# ARM_Arduino_Mega_Board_v2.net
KiCad netlist of a schematic drawn in EAGLE
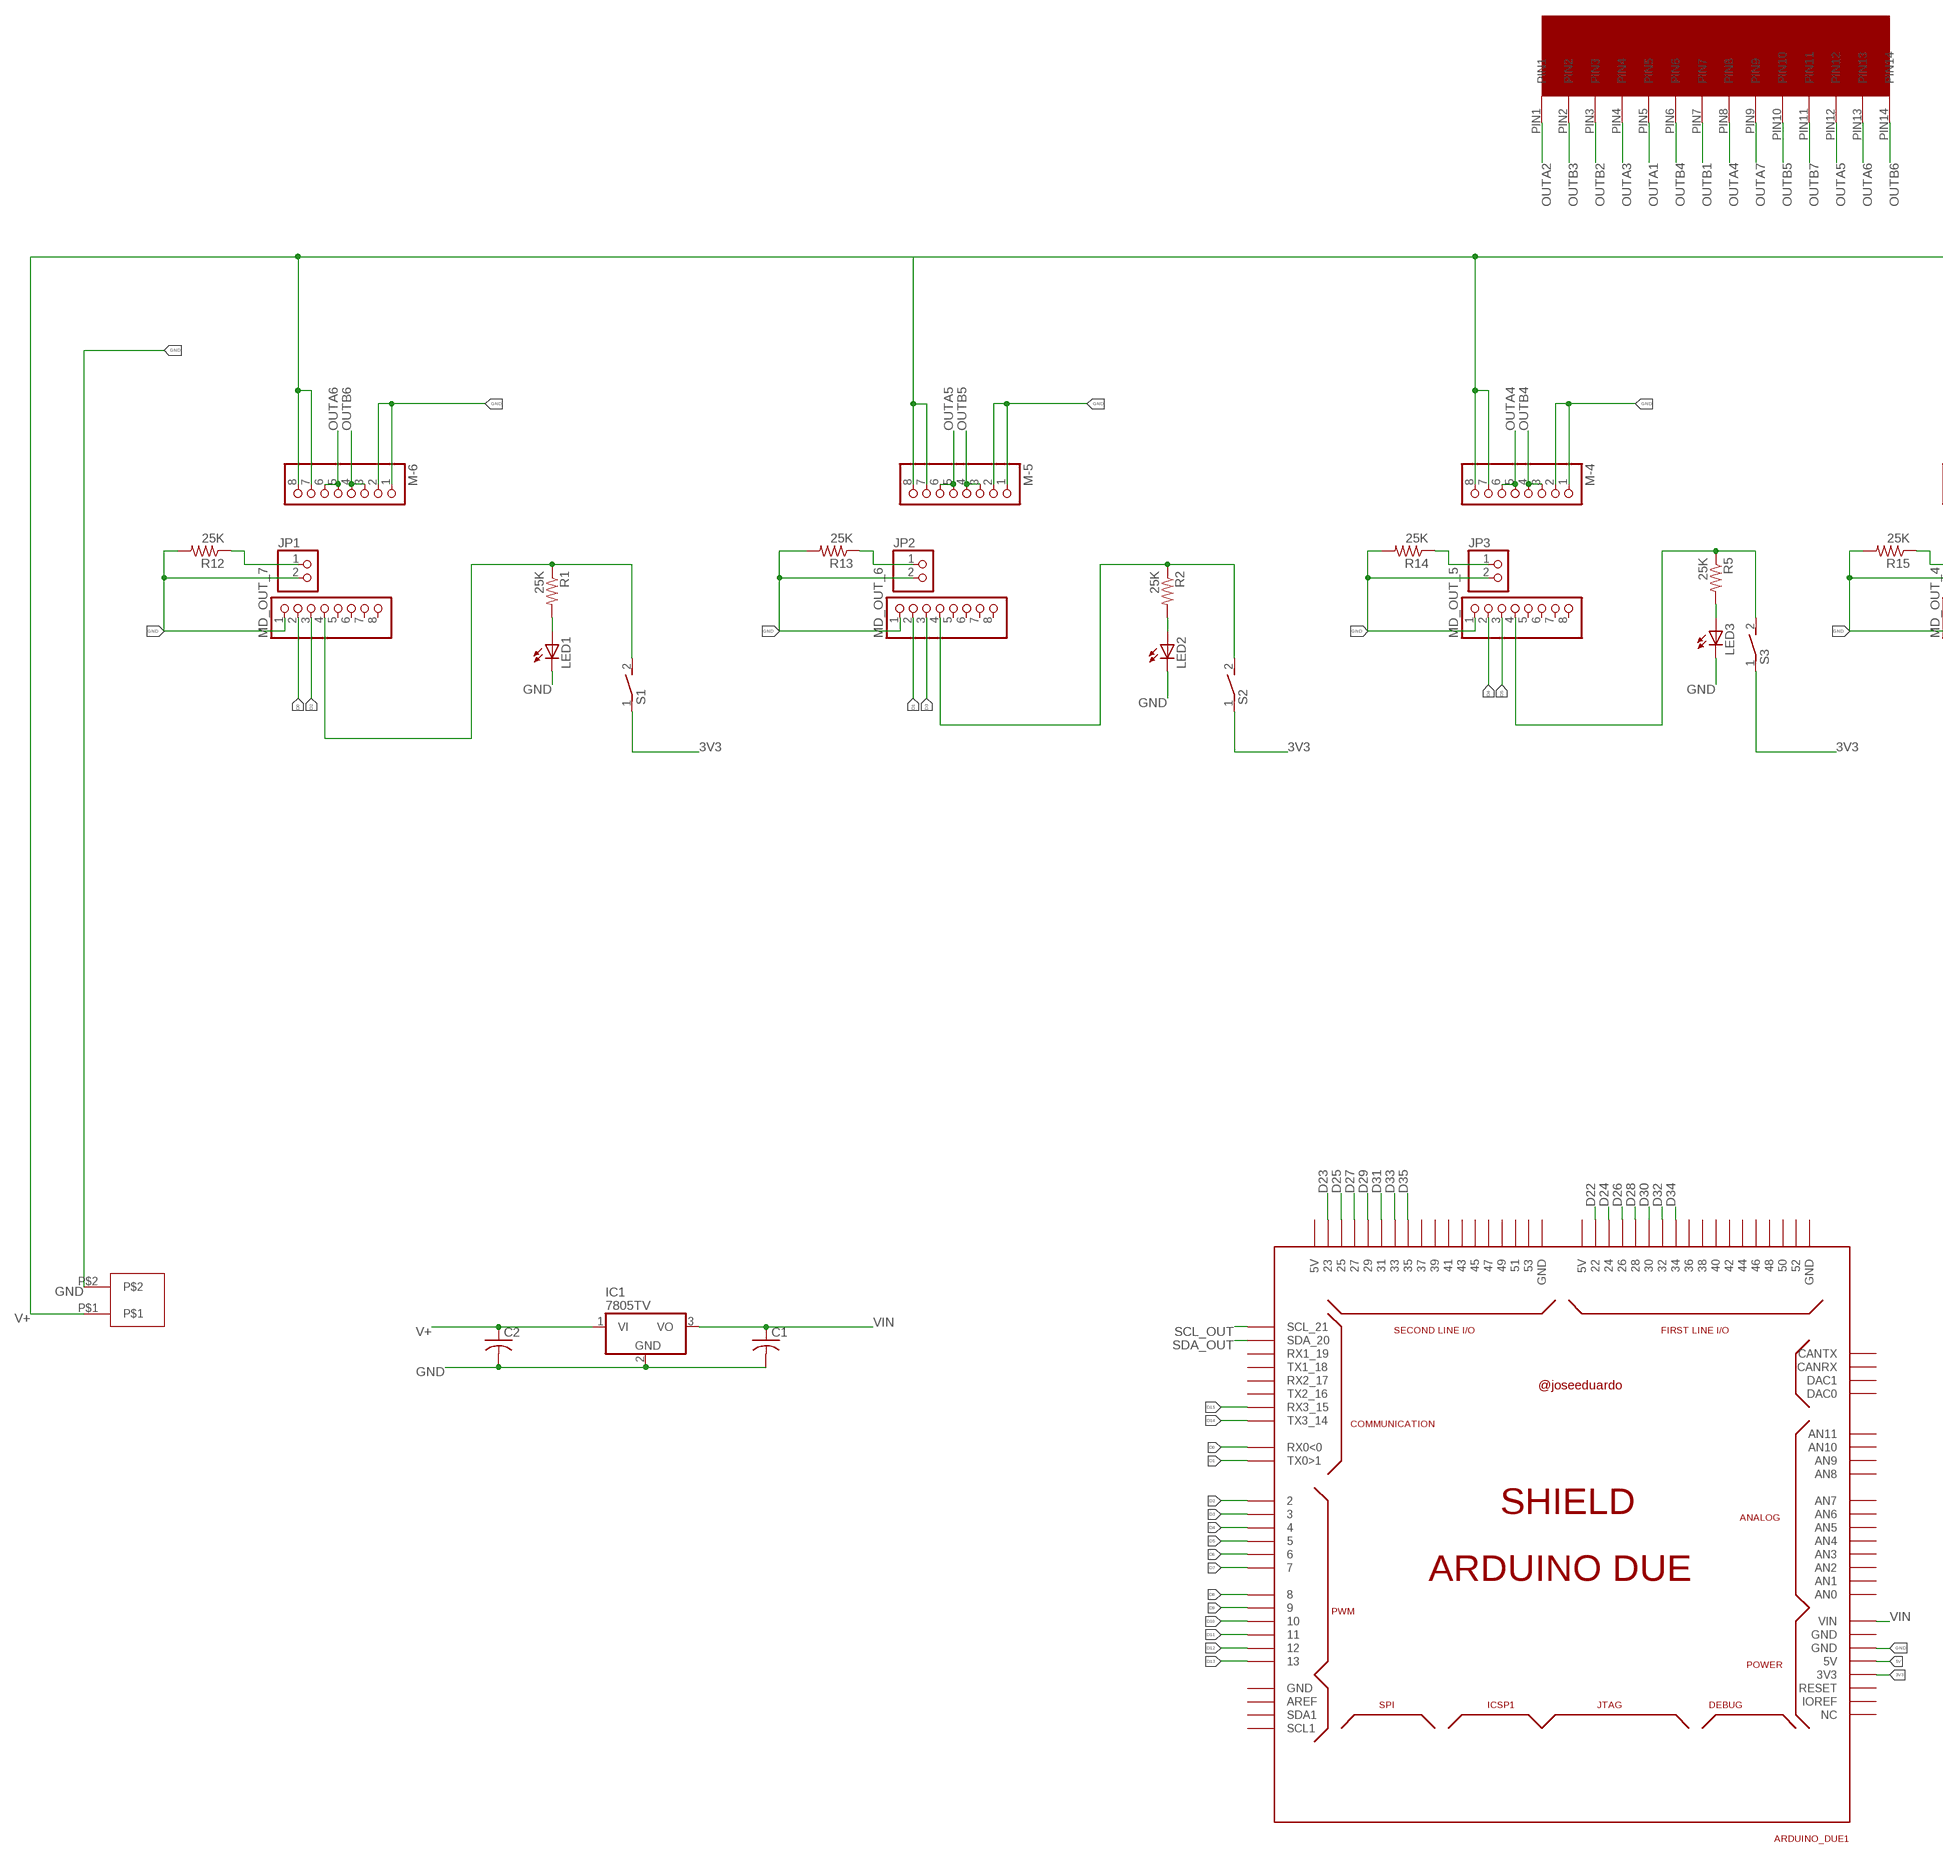
[diagram p0: schematic, sheet 1, part 1 of 2]
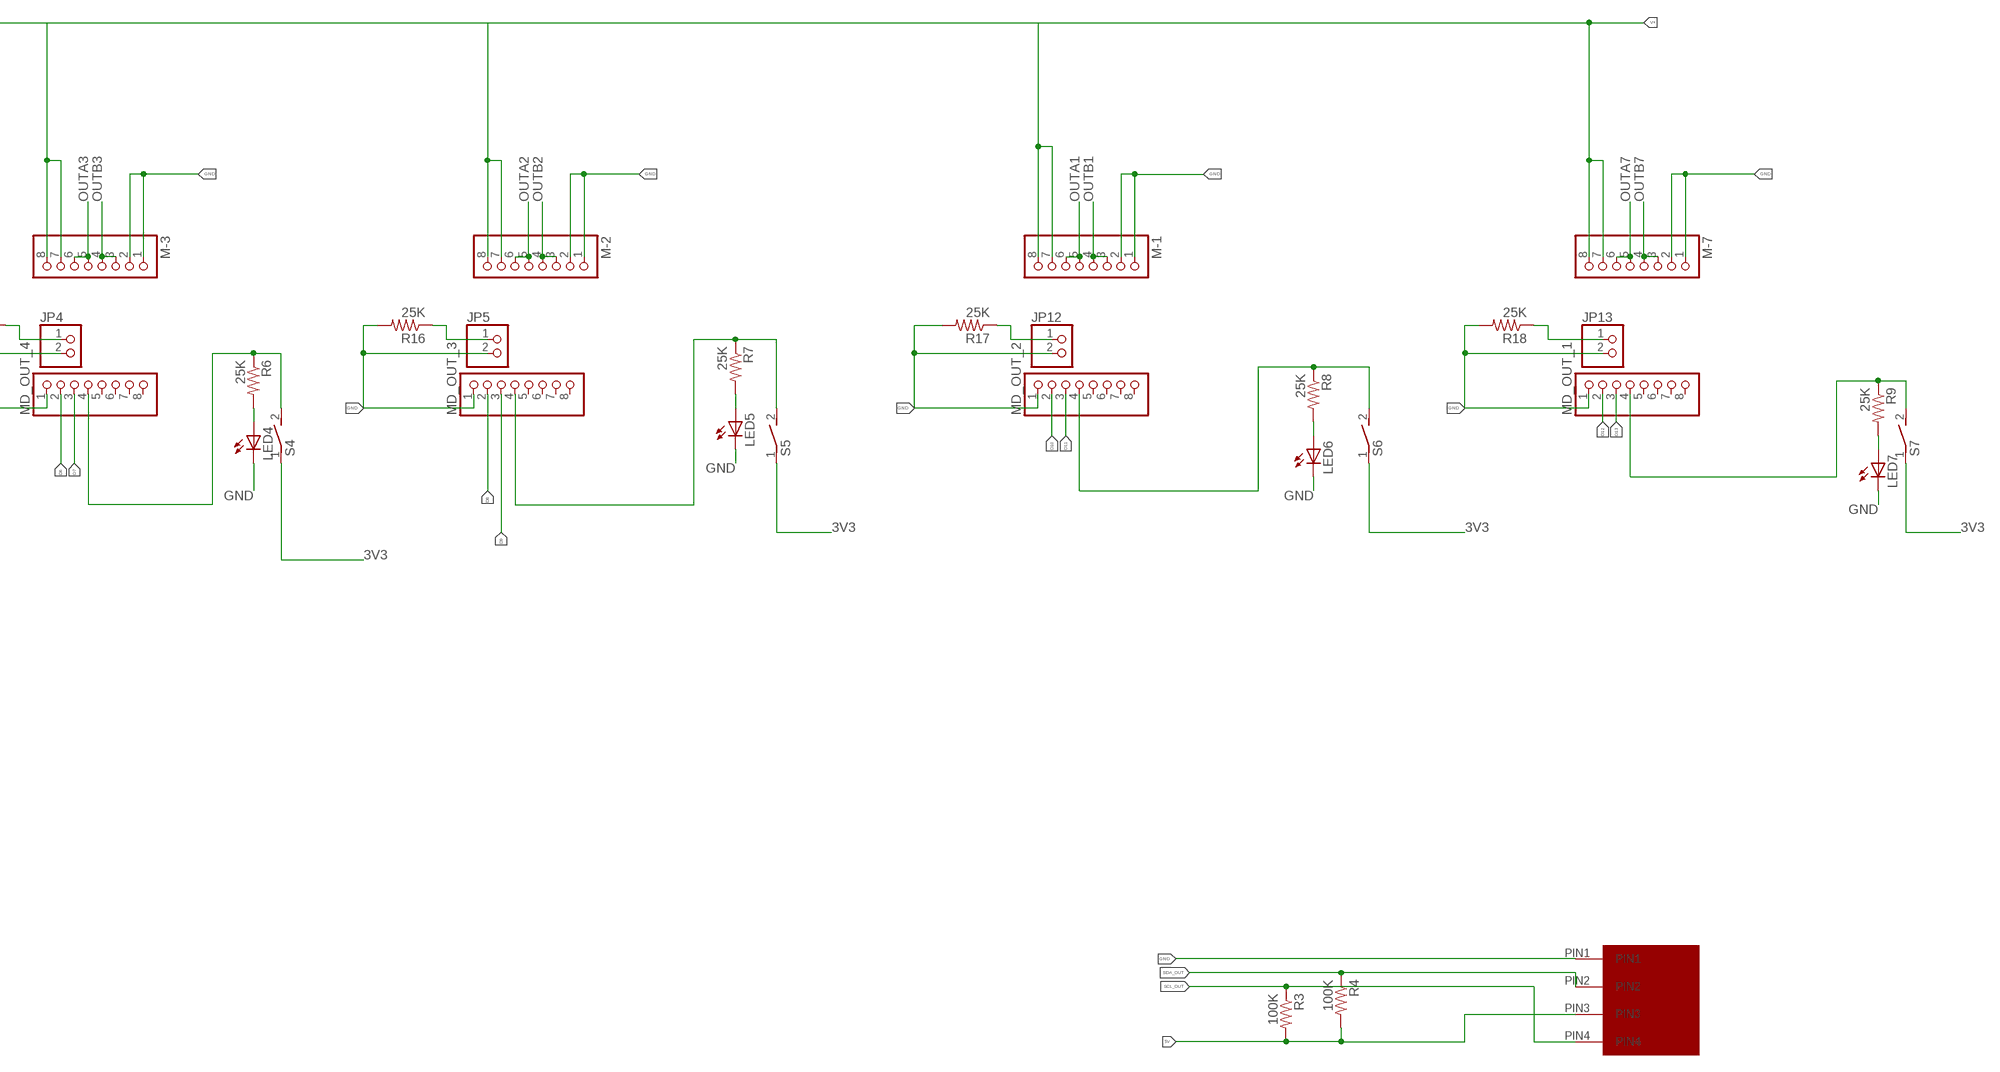
[diagram p1: schematic, sheet 1, part 2 of 2]

(export (version "E")
  (design (tool "Eeschema 10.0.6"))
  (components
    (comp (ref "ARDUINO_DUE1")
      (value "ARDUINO_DUE_SHIELD")
      (footprint "eagle-import:ARDUINO_DUE_SHIELD")
      (libsource (lib "eagle-import") (part "ARDUINO_DUE_SHIELD"))
    )
    (comp (ref "C1")
      (value "C-US050-045X075")
      (footprint "eagle-import:C050-045X075")
      (libsource (lib "eagle-import") (part "C-US050-045X075"))
    )
    (comp (ref "C2")
      (value "C-US050-045X075")
      (footprint "eagle-import:C050-045X075")
      (libsource (lib "eagle-import") (part "C-US050-045X075"))
    )
    (comp (ref "IC1")
      (value "7805TV")
      (footprint "eagle-import:TO220V")
      (libsource (lib "eagle-import") (part "78TV05"))
    )
    (comp (ref "JP1")
      (value "PINHD-1X2")
      (footprint "eagle-import:1X02")
      (libsource (lib "eagle-import") (part "PINHD-1X2"))
    )
    (comp (ref "JP2")
      (value "PINHD-1X2")
      (footprint "eagle-import:1X02")
      (libsource (lib "eagle-import") (part "PINHD-1X2"))
    )
    (comp (ref "JP3")
      (value "PINHD-1X2")
      (footprint "eagle-import:1X02")
      (libsource (lib "eagle-import") (part "PINHD-1X2"))
    )
    (comp (ref "JP4")
      (value "PINHD-1X2")
      (footprint "eagle-import:1X02")
      (libsource (lib "eagle-import") (part "PINHD-1X2"))
    )
    (comp (ref "JP5")
      (value "PINHD-1X2")
      (footprint "eagle-import:1X02")
      (libsource (lib "eagle-import") (part "PINHD-1X2"))
    )
    (comp (ref "JP12")
      (value "PINHD-1X2")
      (footprint "eagle-import:1X02")
      (libsource (lib "eagle-import") (part "PINHD-1X2"))
    )
    (comp (ref "JP13")
      (value "PINHD-1X2")
      (footprint "eagle-import:1X02")
      (libsource (lib "eagle-import") (part "PINHD-1X2"))
    )
    (comp (ref "LED1")
      (value "LEDCHIP-LED0603")
      (footprint "eagle-import:CHIP-LED0603")
      (libsource (lib "eagle-import") (part "LEDCHIP-LED0603"))
    )
    (comp (ref "LED2")
      (value "LEDCHIP-LED0603")
      (footprint "eagle-import:CHIP-LED0603")
      (libsource (lib "eagle-import") (part "LEDCHIP-LED0603"))
    )
    (comp (ref "LED3")
      (value "LEDCHIP-LED0603")
      (footprint "eagle-import:CHIP-LED0603")
      (libsource (lib "eagle-import") (part "LEDCHIP-LED0603"))
    )
    (comp (ref "LED4")
      (value "LEDCHIP-LED0603")
      (footprint "eagle-import:CHIP-LED0603")
      (libsource (lib "eagle-import") (part "LEDCHIP-LED0603"))
    )
    (comp (ref "LED5")
      (value "LEDCHIP-LED0603")
      (footprint "eagle-import:CHIP-LED0603")
      (libsource (lib "eagle-import") (part "LEDCHIP-LED0603"))
    )
    (comp (ref "LED6")
      (value "LEDCHIP-LED0603")
      (footprint "eagle-import:CHIP-LED0603")
      (libsource (lib "eagle-import") (part "LEDCHIP-LED0603"))
    )
    (comp (ref "LED7")
      (value "LEDCHIP-LED0603")
      (footprint "eagle-import:CHIP-LED0603")
      (libsource (lib "eagle-import") (part "LEDCHIP-LED0603"))
    )
    (comp (ref "M-1")
      (value "PINHD-1X8")
      (footprint "eagle-import:1X08")
      (libsource (lib "eagle-import") (part "PINHD-1X8"))
    )
    (comp (ref "M-2")
      (value "PINHD-1X8")
      (footprint "eagle-import:1X08")
      (libsource (lib "eagle-import") (part "PINHD-1X8"))
    )
    (comp (ref "M-3")
      (value "PINHD-1X8")
      (footprint "eagle-import:1X08")
      (libsource (lib "eagle-import") (part "PINHD-1X8"))
    )
    (comp (ref "M-4")
      (value "PINHD-1X8")
      (footprint "eagle-import:1X08")
      (libsource (lib "eagle-import") (part "PINHD-1X8"))
    )
    (comp (ref "M-5")
      (value "PINHD-1X8")
      (footprint "eagle-import:1X08")
      (libsource (lib "eagle-import") (part "PINHD-1X8"))
    )
    (comp (ref "M-6")
      (value "PINHD-1X8")
      (footprint "eagle-import:1X08")
      (libsource (lib "eagle-import") (part "PINHD-1X8"))
    )
    (comp (ref "M-7")
      (value "PINHD-1X8")
      (footprint "eagle-import:1X08")
      (libsource (lib "eagle-import") (part "PINHD-1X8"))
    )
    (comp (ref "MD_OUT_1")
      (value "PINHD-1X8")
      (footprint "eagle-import:1X08")
      (libsource (lib "eagle-import") (part "PINHD-1X8"))
    )
    (comp (ref "MD_OUT_2")
      (value "PINHD-1X8")
      (footprint "eagle-import:1X08")
      (libsource (lib "eagle-import") (part "PINHD-1X8"))
    )
    (comp (ref "MD_OUT_3")
      (value "PINHD-1X8")
      (footprint "eagle-import:1X08")
      (libsource (lib "eagle-import") (part "PINHD-1X8"))
    )
    (comp (ref "MD_OUT_4")
      (value "PINHD-1X8")
      (footprint "eagle-import:1X08")
      (libsource (lib "eagle-import") (part "PINHD-1X8"))
    )
    (comp (ref "MD_OUT_5")
      (value "PINHD-1X8")
      (footprint "eagle-import:1X08")
      (libsource (lib "eagle-import") (part "PINHD-1X8"))
    )
    (comp (ref "MD_OUT_6")
      (value "PINHD-1X8")
      (footprint "eagle-import:1X08")
      (libsource (lib "eagle-import") (part "PINHD-1X8"))
    )
    (comp (ref "MD_OUT_7")
      (value "PINHD-1X8")
      (footprint "eagle-import:1X08")
      (libsource (lib "eagle-import") (part "PINHD-1X8"))
    )
    (comp (ref "R1")
      (value "25K")
      (footprint "eagle-import:R0603")
      (libsource (lib "eagle-import") (part "R-US_R0603"))
    )
    (comp (ref "R2")
      (value "25K")
      (footprint "eagle-import:R0603")
      (libsource (lib "eagle-import") (part "R-US_R0603"))
    )
    (comp (ref "R3")
      (value "100K")
      (footprint "eagle-import:R0603")
      (libsource (lib "eagle-import") (part "R-US_R0603"))
    )
    (comp (ref "R4")
      (value "100K")
      (footprint "eagle-import:R0603")
      (libsource (lib "eagle-import") (part "R-US_R0603"))
    )
    (comp (ref "R5")
      (value "25K")
      (footprint "eagle-import:R0603")
      (libsource (lib "eagle-import") (part "R-US_R0603"))
    )
    (comp (ref "R6")
      (value "25K")
      (footprint "eagle-import:R0603")
      (libsource (lib "eagle-import") (part "R-US_R0603"))
    )
    (comp (ref "R7")
      (value "25K")
      (footprint "eagle-import:R0603")
      (libsource (lib "eagle-import") (part "R-US_R0603"))
    )
    (comp (ref "R8")
      (value "25K")
      (footprint "eagle-import:R0603")
      (libsource (lib "eagle-import") (part "R-US_R0603"))
    )
    (comp (ref "R9")
      (value "25K")
      (footprint "eagle-import:R0603")
      (libsource (lib "eagle-import") (part "R-US_R0603"))
    )
    (comp (ref "R12")
      (value "25K")
      (footprint "eagle-import:R0603")
      (libsource (lib "eagle-import") (part "R-US_R0603"))
    )
    (comp (ref "R13")
      (value "25K")
      (footprint "eagle-import:R0603")
      (libsource (lib "eagle-import") (part "R-US_R0603"))
    )
    (comp (ref "R14")
      (value "25K")
      (footprint "eagle-import:R0603")
      (libsource (lib "eagle-import") (part "R-US_R0603"))
    )
    (comp (ref "R15")
      (value "25K")
      (footprint "eagle-import:R0603")
      (libsource (lib "eagle-import") (part "R-US_R0603"))
    )
    (comp (ref "R16")
      (value "25K")
      (footprint "eagle-import:R0603")
      (libsource (lib "eagle-import") (part "R-US_R0603"))
    )
    (comp (ref "R17")
      (value "25K")
      (footprint "eagle-import:R0603")
      (libsource (lib "eagle-import") (part "R-US_R0603"))
    )
    (comp (ref "R18")
      (value "25K")
      (footprint "eagle-import:R0603")
      (libsource (lib "eagle-import") (part "R-US_R0603"))
    )
    (comp (ref "S1")
      (value "DS01E")
      (footprint "eagle-import:DS-01")
      (libsource (lib "eagle-import") (part "DS01E"))
    )
    (comp (ref "S2")
      (value "DS01E")
      (footprint "eagle-import:DS-01")
      (libsource (lib "eagle-import") (part "DS01E"))
    )
    (comp (ref "S3")
      (value "DS01E")
      (footprint "eagle-import:DS-01")
      (libsource (lib "eagle-import") (part "DS01E"))
    )
    (comp (ref "S4")
      (value "DS01E")
      (footprint "eagle-import:DS-01")
      (libsource (lib "eagle-import") (part "DS01E"))
    )
    (comp (ref "S5")
      (value "DS01E")
      (footprint "eagle-import:DS-01")
      (libsource (lib "eagle-import") (part "DS01E"))
    )
    (comp (ref "S6")
      (value "DS01E")
      (footprint "eagle-import:DS-01")
      (libsource (lib "eagle-import") (part "DS01E"))
    )
    (comp (ref "S7")
      (value "DS01E")
      (footprint "eagle-import:DS-01")
      (libsource (lib "eagle-import") (part "DS01E"))
    )
    (comp (ref "U$1")
      (value "MEGA-FIT_RA_2")
      (footprint "eagle-import:MEGA-FIT_RA_2")
      (libsource (lib "eagle-import") (part "MEGA-FIT_RA_2"))
    )
    (comp (ref "U$2")
      (value "14PINULTRAFIT")
      (footprint "eagle-import:14PINULTRAFIT")
      (libsource (lib "eagle-import") (part "14PINULTRAFIT"))
    )
    (comp (ref "U$3")
      (value "4PIN_ULTRA_FIT")
      (footprint "eagle-import:4PIN_ULTRA_FIT")
      (libsource (lib "eagle-import") (part "4PIN_ULTRA_FIT"))
    )
  )
  (nets
    (net (code "1") (name "/D22") (class "Default")
      (node (ref "ARDUINO_DUE1") (pin "22") (pinfunction "22_22") (pintype "bidirectional"))
    )
    (net (code "2") (name "/D23") (class "Default")
      (node (ref "ARDUINO_DUE1") (pin "23") (pinfunction "23_23") (pintype "bidirectional"))
    )
    (net (code "3") (name "/D24") (class "Default")
      (node (ref "ARDUINO_DUE1") (pin "24") (pinfunction "24_24") (pintype "bidirectional"))
    )
    (net (code "4") (name "/D25") (class "Default")
      (node (ref "ARDUINO_DUE1") (pin "25") (pinfunction "25_25") (pintype "bidirectional"))
    )
    (net (code "5") (name "/D26") (class "Default")
      (node (ref "ARDUINO_DUE1") (pin "26") (pinfunction "26_26") (pintype "bidirectional"))
    )
    (net (code "6") (name "/D27") (class "Default")
      (node (ref "ARDUINO_DUE1") (pin "27") (pinfunction "27_27") (pintype "bidirectional"))
    )
    (net (code "7") (name "/D28") (class "Default")
      (node (ref "ARDUINO_DUE1") (pin "28") (pinfunction "28_28") (pintype "bidirectional"))
    )
    (net (code "8") (name "/D29") (class "Default")
      (node (ref "ARDUINO_DUE1") (pin "29") (pinfunction "29_29") (pintype "bidirectional"))
    )
    (net (code "9") (name "/D30") (class "Default")
      (node (ref "ARDUINO_DUE1") (pin "30") (pinfunction "30_30") (pintype "bidirectional"))
    )
    (net (code "10") (name "/D31") (class "Default")
      (node (ref "ARDUINO_DUE1") (pin "31") (pinfunction "31_31") (pintype "bidirectional"))
    )
    (net (code "11") (name "/D32") (class "Default")
      (node (ref "ARDUINO_DUE1") (pin "32") (pinfunction "32_32") (pintype "bidirectional"))
    )
    (net (code "12") (name "/D33") (class "Default")
      (node (ref "ARDUINO_DUE1") (pin "33") (pinfunction "33_33") (pintype "bidirectional"))
    )
    (net (code "13") (name "/D34") (class "Default")
      (node (ref "ARDUINO_DUE1") (pin "34") (pinfunction "34_34") (pintype "bidirectional"))
    )
    (net (code "14") (name "/D35") (class "Default")
      (node (ref "ARDUINO_DUE1") (pin "35") (pinfunction "35_35") (pintype "bidirectional"))
    )
    (net (code "15") (name "/OUTA1") (class "Default")
      (node (ref "M-1") (pin "5") (pinfunction "5_5") (pintype "passive"))
      (node (ref "M-1") (pin "6") (pinfunction "6_6") (pintype "passive"))
      (node (ref "U$2") (pin "PIN5") (pinfunction "PIN5_PIN5") (pintype "bidirectional"))
    )
    (net (code "16") (name "/OUTA2") (class "Default")
      (node (ref "M-2") (pin "5") (pinfunction "5_5") (pintype "passive"))
      (node (ref "M-2") (pin "6") (pinfunction "6_6") (pintype "passive"))
      (node (ref "U$2") (pin "PIN1") (pinfunction "PIN1_PIN1") (pintype "bidirectional"))
    )
    (net (code "17") (name "/OUTA3") (class "Default")
      (node (ref "M-3") (pin "5") (pinfunction "5_5") (pintype "passive"))
      (node (ref "M-3") (pin "6") (pinfunction "6_6") (pintype "passive"))
      (node (ref "U$2") (pin "PIN4") (pinfunction "PIN4_PIN4") (pintype "bidirectional"))
    )
    (net (code "18") (name "/OUTA4") (class "Default")
      (node (ref "M-4") (pin "5") (pinfunction "5_5") (pintype "passive"))
      (node (ref "M-4") (pin "6") (pinfunction "6_6") (pintype "passive"))
      (node (ref "U$2") (pin "PIN8") (pinfunction "PIN8_PIN8") (pintype "bidirectional"))
    )
    (net (code "19") (name "/OUTA5") (class "Default")
      (node (ref "M-5") (pin "5") (pinfunction "5_5") (pintype "passive"))
      (node (ref "M-5") (pin "6") (pinfunction "6_6") (pintype "passive"))
      (node (ref "U$2") (pin "PIN12") (pinfunction "PIN12_PIN12") (pintype "bidirectional"))
    )
    (net (code "20") (name "/OUTA6") (class "Default")
      (node (ref "M-6") (pin "5") (pinfunction "5_5") (pintype "passive"))
      (node (ref "M-6") (pin "6") (pinfunction "6_6") (pintype "passive"))
      (node (ref "U$2") (pin "PIN13") (pinfunction "PIN13_PIN13") (pintype "bidirectional"))
    )
    (net (code "21") (name "/OUTA7") (class "Default")
      (node (ref "M-7") (pin "5") (pinfunction "5_5") (pintype "passive"))
      (node (ref "M-7") (pin "6") (pinfunction "6_6") (pintype "passive"))
      (node (ref "U$2") (pin "PIN9") (pinfunction "PIN9_PIN9") (pintype "bidirectional"))
    )
    (net (code "22") (name "/OUTB1") (class "Default")
      (node (ref "M-1") (pin "3") (pinfunction "3_3") (pintype "passive"))
      (node (ref "M-1") (pin "4") (pinfunction "4_4") (pintype "passive"))
      (node (ref "U$2") (pin "PIN7") (pinfunction "PIN7_PIN7") (pintype "bidirectional"))
    )
    (net (code "23") (name "/OUTB2") (class "Default")
      (node (ref "M-2") (pin "3") (pinfunction "3_3") (pintype "passive"))
      (node (ref "M-2") (pin "4") (pinfunction "4_4") (pintype "passive"))
      (node (ref "U$2") (pin "PIN3") (pinfunction "PIN3_PIN3") (pintype "bidirectional"))
    )
    (net (code "24") (name "/OUTB3") (class "Default")
      (node (ref "M-3") (pin "3") (pinfunction "3_3") (pintype "passive"))
      (node (ref "M-3") (pin "4") (pinfunction "4_4") (pintype "passive"))
      (node (ref "U$2") (pin "PIN2") (pinfunction "PIN2_PIN2") (pintype "bidirectional"))
    )
    (net (code "25") (name "/OUTB4") (class "Default")
      (node (ref "M-4") (pin "3") (pinfunction "3_3") (pintype "passive"))
      (node (ref "M-4") (pin "4") (pinfunction "4_4") (pintype "passive"))
      (node (ref "U$2") (pin "PIN6") (pinfunction "PIN6_PIN6") (pintype "bidirectional"))
    )
    (net (code "26") (name "/OUTB5") (class "Default")
      (node (ref "M-5") (pin "3") (pinfunction "3_3") (pintype "passive"))
      (node (ref "M-5") (pin "4") (pinfunction "4_4") (pintype "passive"))
      (node (ref "U$2") (pin "PIN10") (pinfunction "PIN10_PIN10") (pintype "bidirectional"))
    )
    (net (code "27") (name "/OUTB6") (class "Default")
      (node (ref "M-6") (pin "3") (pinfunction "3_3") (pintype "passive"))
      (node (ref "M-6") (pin "4") (pinfunction "4_4") (pintype "passive"))
      (node (ref "U$2") (pin "PIN14") (pinfunction "PIN14_PIN14") (pintype "bidirectional"))
    )
    (net (code "28") (name "/OUTB7") (class "Default")
      (node (ref "M-7") (pin "3") (pinfunction "3_3") (pintype "passive"))
      (node (ref "M-7") (pin "4") (pinfunction "4_4") (pintype "passive"))
      (node (ref "U$2") (pin "PIN11") (pinfunction "PIN11_PIN11") (pintype "bidirectional"))
    )
    (net (code "29") (name "/VIN") (class "Default")
      (node (ref "ARDUINO_DUE1") (pin "VIN") (pinfunction "VIN_VIN") (pintype "bidirectional"))
      (node (ref "C1") (pin "1") (pinfunction "1_1") (pintype "passive"))
      (node (ref "IC1") (pin "3") (pinfunction "VO_3") (pintype "passive"))
    )
    (net (code "30") (name "3V3") (class "Default")
      (node (ref "ARDUINO_DUE1") (pin "3V3") (pinfunction "3V3_3V3") (pintype "bidirectional"))
      (node (ref "S1") (pin "1") (pinfunction "1_1") (pintype "passive"))
      (node (ref "S2") (pin "1") (pinfunction "1_1") (pintype "passive"))
      (node (ref "S3") (pin "1") (pinfunction "1_1") (pintype "passive"))
      (node (ref "S4") (pin "1") (pinfunction "1_1") (pintype "passive"))
      (node (ref "S5") (pin "1") (pinfunction "1_1") (pintype "passive"))
      (node (ref "S6") (pin "1") (pinfunction "1_1") (pintype "passive"))
      (node (ref "S7") (pin "1") (pinfunction "1_1") (pintype "passive"))
    )
    (net (code "31") (name "5V") (class "Default")
      (node (ref "ARDUINO_DUE1") (pin "5V0") (pinfunction "5V_5V0") (pintype "bidirectional"))
      (node (ref "R3") (pin "2") (pinfunction "2_2") (pintype "passive"))
      (node (ref "R4") (pin "2") (pinfunction "2_2") (pintype "passive"))
      (node (ref "U$3") (pin "PIN3") (pinfunction "PIN3_PIN3") (pintype "bidirectional"))
    )
    (net (code "32") (name "D0") (class "Default")
      (node (ref "ARDUINO_DUE1") (pin "0") (pinfunction "RX0<0_0") (pintype "bidirectional"))
      (node (ref "MD_OUT_7") (pin "2") (pinfunction "2_2") (pintype "passive"))
    )
    (net (code "33") (name "D1") (class "Default")
      (node (ref "ARDUINO_DUE1") (pin "1") (pinfunction "TX0>1_1") (pintype "bidirectional"))
      (node (ref "MD_OUT_6") (pin "2") (pinfunction "2_2") (pintype "passive"))
    )
    (net (code "34") (name "D2") (class "Default")
      (node (ref "ARDUINO_DUE1") (pin "2") (pinfunction "2_2") (pintype "bidirectional"))
      (node (ref "MD_OUT_7") (pin "3") (pinfunction "3_3") (pintype "passive"))
    )
    (net (code "35") (name "D3") (class "Default")
      (node (ref "ARDUINO_DUE1") (pin "3") (pinfunction "3_3") (pintype "bidirectional"))
      (node (ref "MD_OUT_6") (pin "3") (pinfunction "3_3") (pintype "passive"))
    )
    (net (code "36") (name "D4") (class "Default")
      (node (ref "ARDUINO_DUE1") (pin "4") (pinfunction "4_4") (pintype "bidirectional"))
      (node (ref "MD_OUT_5") (pin "2") (pinfunction "2_2") (pintype "passive"))
    )
    (net (code "37") (name "D5") (class "Default")
      (node (ref "ARDUINO_DUE1") (pin "5") (pinfunction "5_5") (pintype "bidirectional"))
      (node (ref "MD_OUT_5") (pin "3") (pinfunction "3_3") (pintype "passive"))
    )
    (net (code "38") (name "D6") (class "Default")
      (node (ref "ARDUINO_DUE1") (pin "6") (pinfunction "6_6") (pintype "bidirectional"))
      (node (ref "MD_OUT_4") (pin "2") (pinfunction "2_2") (pintype "passive"))
    )
    (net (code "39") (name "D7") (class "Default")
      (node (ref "ARDUINO_DUE1") (pin "7") (pinfunction "7_7") (pintype "bidirectional"))
      (node (ref "MD_OUT_4") (pin "3") (pinfunction "3_3") (pintype "passive"))
    )
    (net (code "40") (name "D8") (class "Default")
      (node (ref "ARDUINO_DUE1") (pin "8") (pinfunction "8_8") (pintype "bidirectional"))
      (node (ref "MD_OUT_3") (pin "2") (pinfunction "2_2") (pintype "passive"))
    )
    (net (code "41") (name "D9") (class "Default")
      (node (ref "ARDUINO_DUE1") (pin "9") (pinfunction "9_9") (pintype "bidirectional"))
      (node (ref "MD_OUT_3") (pin "3") (pinfunction "3_3") (pintype "passive"))
    )
    (net (code "42") (name "D10") (class "Default")
      (node (ref "ARDUINO_DUE1") (pin "10") (pinfunction "10_10") (pintype "bidirectional"))
      (node (ref "MD_OUT_2") (pin "2") (pinfunction "2_2") (pintype "passive"))
    )
    (net (code "43") (name "D11") (class "Default")
      (node (ref "ARDUINO_DUE1") (pin "11") (pinfunction "11_11") (pintype "bidirectional"))
      (node (ref "MD_OUT_2") (pin "3") (pinfunction "3_3") (pintype "passive"))
    )
    (net (code "44") (name "D12") (class "Default")
      (node (ref "ARDUINO_DUE1") (pin "12") (pinfunction "12_12") (pintype "bidirectional"))
      (node (ref "MD_OUT_1") (pin "2") (pinfunction "2_2") (pintype "passive"))
    )
    (net (code "45") (name "D13") (class "Default")
      (node (ref "ARDUINO_DUE1") (pin "13") (pinfunction "13_13") (pintype "bidirectional"))
      (node (ref "MD_OUT_1") (pin "3") (pinfunction "3_3") (pintype "passive"))
    )
    (net (code "46") (name "D14") (class "Default")
      (node (ref "ARDUINO_DUE1") (pin "14") (pinfunction "TX3_14_14") (pintype "bidirectional"))
    )
    (net (code "47") (name "D15") (class "Default")
      (node (ref "ARDUINO_DUE1") (pin "15") (pinfunction "RX3_15_15") (pintype "bidirectional"))
    )
    (net (code "48") (name "GND") (class "Default")
      (node (ref "ARDUINO_DUE1") (pin "GND") (pinfunction "GND_GND") (pintype "bidirectional"))
      (node (ref "C1") (pin "2") (pinfunction "2_2") (pintype "passive"))
      (node (ref "C2") (pin "2") (pinfunction "2_2") (pintype "passive"))
      (node (ref "IC1") (pin "2") (pinfunction "GND_2") (pintype "passive"))
      (node (ref "JP1") (pin "2") (pinfunction "2_2") (pintype "passive"))
      (node (ref "JP12") (pin "2") (pinfunction "2_2") (pintype "passive"))
      (node (ref "JP13") (pin "2") (pinfunction "2_2") (pintype "passive"))
      (node (ref "JP2") (pin "2") (pinfunction "2_2") (pintype "passive"))
      (node (ref "JP3") (pin "2") (pinfunction "2_2") (pintype "passive"))
      (node (ref "JP4") (pin "2") (pinfunction "2_2") (pintype "passive"))
      (node (ref "JP5") (pin "2") (pinfunction "2_2") (pintype "passive"))
      (node (ref "LED1") (pin "C") (pinfunction "C_C") (pintype "passive"))
      (node (ref "LED2") (pin "C") (pinfunction "C_C") (pintype "passive"))
      (node (ref "LED3") (pin "C") (pinfunction "C_C") (pintype "passive"))
      (node (ref "LED4") (pin "C") (pinfunction "C_C") (pintype "passive"))
      (node (ref "LED5") (pin "C") (pinfunction "C_C") (pintype "passive"))
      (node (ref "LED6") (pin "C") (pinfunction "C_C") (pintype "passive"))
      (node (ref "LED7") (pin "C") (pinfunction "C_C") (pintype "passive"))
      (node (ref "M-1") (pin "1") (pinfunction "1_1") (pintype "passive"))
      (node (ref "M-1") (pin "2") (pinfunction "2_2") (pintype "passive"))
      (node (ref "M-2") (pin "1") (pinfunction "1_1") (pintype "passive"))
      (node (ref "M-2") (pin "2") (pinfunction "2_2") (pintype "passive"))
      (node (ref "M-3") (pin "1") (pinfunction "1_1") (pintype "passive"))
      (node (ref "M-3") (pin "2") (pinfunction "2_2") (pintype "passive"))
      (node (ref "M-4") (pin "1") (pinfunction "1_1") (pintype "passive"))
      (node (ref "M-4") (pin "2") (pinfunction "2_2") (pintype "passive"))
      (node (ref "M-5") (pin "1") (pinfunction "1_1") (pintype "passive"))
      (node (ref "M-5") (pin "2") (pinfunction "2_2") (pintype "passive"))
      (node (ref "M-6") (pin "1") (pinfunction "1_1") (pintype "passive"))
      (node (ref "M-6") (pin "2") (pinfunction "2_2") (pintype "passive"))
      (node (ref "M-7") (pin "1") (pinfunction "1_1") (pintype "passive"))
      (node (ref "M-7") (pin "2") (pinfunction "2_2") (pintype "passive"))
      (node (ref "MD_OUT_1") (pin "1") (pinfunction "1_1") (pintype "passive"))
      (node (ref "MD_OUT_2") (pin "1") (pinfunction "1_1") (pintype "passive"))
      (node (ref "MD_OUT_3") (pin "1") (pinfunction "1_1") (pintype "passive"))
      (node (ref "MD_OUT_4") (pin "1") (pinfunction "1_1") (pintype "passive"))
      (node (ref "MD_OUT_5") (pin "1") (pinfunction "1_1") (pintype "passive"))
      (node (ref "MD_OUT_6") (pin "1") (pinfunction "1_1") (pintype "passive"))
      (node (ref "MD_OUT_7") (pin "1") (pinfunction "1_1") (pintype "passive"))
      (node (ref "R12") (pin "2") (pinfunction "2_2") (pintype "passive"))
      (node (ref "R13") (pin "2") (pinfunction "2_2") (pintype "passive"))
      (node (ref "R14") (pin "2") (pinfunction "2_2") (pintype "passive"))
      (node (ref "R15") (pin "2") (pinfunction "2_2") (pintype "passive"))
      (node (ref "R16") (pin "2") (pinfunction "2_2") (pintype "passive"))
      (node (ref "R17") (pin "2") (pinfunction "2_2") (pintype "passive"))
      (node (ref "R18") (pin "2") (pinfunction "2_2") (pintype "passive"))
      (node (ref "U$1") (pin "P$2") (pinfunction "P$2_P$2") (pintype "bidirectional"))
      (node (ref "U$3") (pin "PIN1") (pinfunction "PIN1_PIN1") (pintype "bidirectional"))
    )
    (net (code "49") (name "Net-(JP1-Pad1)") (class "Default")
      (node (ref "JP1") (pin "1") (pinfunction "1_1") (pintype "passive"))
      (node (ref "R12") (pin "1") (pinfunction "1_1") (pintype "passive"))
    )
    (net (code "50") (name "Net-(JP2-Pad1)") (class "Default")
      (node (ref "JP2") (pin "1") (pinfunction "1_1") (pintype "passive"))
      (node (ref "R13") (pin "1") (pinfunction "1_1") (pintype "passive"))
    )
    (net (code "51") (name "Net-(JP3-Pad1)") (class "Default")
      (node (ref "JP3") (pin "1") (pinfunction "1_1") (pintype "passive"))
      (node (ref "R14") (pin "1") (pinfunction "1_1") (pintype "passive"))
    )
    (net (code "52") (name "Net-(JP4-Pad1)") (class "Default")
      (node (ref "JP4") (pin "1") (pinfunction "1_1") (pintype "passive"))
      (node (ref "R15") (pin "1") (pinfunction "1_1") (pintype "passive"))
    )
    (net (code "53") (name "Net-(JP5-Pad1)") (class "Default")
      (node (ref "JP5") (pin "1") (pinfunction "1_1") (pintype "passive"))
      (node (ref "R16") (pin "1") (pinfunction "1_1") (pintype "passive"))
    )
    (net (code "54") (name "Net-(JP12-Pad1)") (class "Default")
      (node (ref "JP12") (pin "1") (pinfunction "1_1") (pintype "passive"))
      (node (ref "R17") (pin "1") (pinfunction "1_1") (pintype "passive"))
    )
    (net (code "55") (name "Net-(JP13-Pad1)") (class "Default")
      (node (ref "JP13") (pin "1") (pinfunction "1_1") (pintype "passive"))
      (node (ref "R18") (pin "1") (pinfunction "1_1") (pintype "passive"))
    )
    (net (code "56") (name "Net-(LED1-PadA)") (class "Default")
      (node (ref "LED1") (pin "A") (pinfunction "A_A") (pintype "passive"))
      (node (ref "R1") (pin "2") (pinfunction "2_2") (pintype "passive"))
    )
    (net (code "57") (name "Net-(LED2-PadA)") (class "Default")
      (node (ref "LED2") (pin "A") (pinfunction "A_A") (pintype "passive"))
      (node (ref "R2") (pin "2") (pinfunction "2_2") (pintype "passive"))
    )
    (net (code "58") (name "Net-(LED3-PadA)") (class "Default")
      (node (ref "LED3") (pin "A") (pinfunction "A_A") (pintype "passive"))
      (node (ref "R5") (pin "2") (pinfunction "2_2") (pintype "passive"))
    )
    (net (code "59") (name "Net-(LED4-PadA)") (class "Default")
      (node (ref "LED4") (pin "A") (pinfunction "A_A") (pintype "passive"))
      (node (ref "R6") (pin "2") (pinfunction "2_2") (pintype "passive"))
    )
    (net (code "60") (name "Net-(LED5-PadA)") (class "Default")
      (node (ref "LED5") (pin "A") (pinfunction "A_A") (pintype "passive"))
      (node (ref "R7") (pin "2") (pinfunction "2_2") (pintype "passive"))
    )
    (net (code "61") (name "Net-(LED6-PadA)") (class "Default")
      (node (ref "LED6") (pin "A") (pinfunction "A_A") (pintype "passive"))
      (node (ref "R8") (pin "2") (pinfunction "2_2") (pintype "passive"))
    )
    (net (code "62") (name "Net-(LED7-PadA)") (class "Default")
      (node (ref "LED7") (pin "A") (pinfunction "A_A") (pintype "passive"))
      (node (ref "R9") (pin "2") (pinfunction "2_2") (pintype "passive"))
    )
    (net (code "63") (name "Net-(MD_OUT_1-Pad4)") (class "Default")
      (node (ref "MD_OUT_1") (pin "4") (pinfunction "4_4") (pintype "passive"))
      (node (ref "R9") (pin "1") (pinfunction "1_1") (pintype "passive"))
      (node (ref "S7") (pin "2") (pinfunction "2_2") (pintype "passive"))
    )
    (net (code "64") (name "Net-(MD_OUT_2-Pad4)") (class "Default")
      (node (ref "MD_OUT_2") (pin "4") (pinfunction "4_4") (pintype "passive"))
      (node (ref "R8") (pin "1") (pinfunction "1_1") (pintype "passive"))
      (node (ref "S6") (pin "2") (pinfunction "2_2") (pintype "passive"))
    )
    (net (code "65") (name "Net-(MD_OUT_3-Pad4)") (class "Default")
      (node (ref "MD_OUT_3") (pin "4") (pinfunction "4_4") (pintype "passive"))
      (node (ref "R7") (pin "1") (pinfunction "1_1") (pintype "passive"))
      (node (ref "S5") (pin "2") (pinfunction "2_2") (pintype "passive"))
    )
    (net (code "66") (name "Net-(MD_OUT_4-Pad4)") (class "Default")
      (node (ref "MD_OUT_4") (pin "4") (pinfunction "4_4") (pintype "passive"))
      (node (ref "R6") (pin "1") (pinfunction "1_1") (pintype "passive"))
      (node (ref "S4") (pin "2") (pinfunction "2_2") (pintype "passive"))
    )
    (net (code "67") (name "Net-(MD_OUT_5-Pad4)") (class "Default")
      (node (ref "MD_OUT_5") (pin "4") (pinfunction "4_4") (pintype "passive"))
      (node (ref "R5") (pin "1") (pinfunction "1_1") (pintype "passive"))
      (node (ref "S3") (pin "2") (pinfunction "2_2") (pintype "passive"))
    )
    (net (code "68") (name "Net-(MD_OUT_6-Pad4)") (class "Default")
      (node (ref "MD_OUT_6") (pin "4") (pinfunction "4_4") (pintype "passive"))
      (node (ref "R2") (pin "1") (pinfunction "1_1") (pintype "passive"))
      (node (ref "S2") (pin "2") (pinfunction "2_2") (pintype "passive"))
    )
    (net (code "69") (name "Net-(MD_OUT_7-Pad4)") (class "Default")
      (node (ref "MD_OUT_7") (pin "4") (pinfunction "4_4") (pintype "passive"))
      (node (ref "R1") (pin "1") (pinfunction "1_1") (pintype "passive"))
      (node (ref "S1") (pin "2") (pinfunction "2_2") (pintype "passive"))
    )
    (net (code "70") (name "SCL_OUT") (class "Default")
      (node (ref "ARDUINO_DUE1") (pin "21") (pinfunction "SCL_21_21") (pintype "bidirectional"))
      (node (ref "R3") (pin "1") (pinfunction "1_1") (pintype "passive"))
      (node (ref "U$3") (pin "PIN4") (pinfunction "PIN4_PIN4") (pintype "bidirectional"))
    )
    (net (code "71") (name "SDA_OUT") (class "Default")
      (node (ref "ARDUINO_DUE1") (pin "20") (pinfunction "SDA_20_20") (pintype "bidirectional"))
      (node (ref "R4") (pin "1") (pinfunction "1_1") (pintype "passive"))
      (node (ref "U$3") (pin "PIN2") (pinfunction "PIN2_PIN2") (pintype "bidirectional"))
    )
    (net (code "72") (name "V+") (class "Default")
      (node (ref "C2") (pin "1") (pinfunction "1_1") (pintype "passive"))
      (node (ref "IC1") (pin "1") (pinfunction "VI_1") (pintype "input"))
      (node (ref "M-1") (pin "7") (pinfunction "7_7") (pintype "passive"))
      (node (ref "M-1") (pin "8") (pinfunction "8_8") (pintype "passive"))
      (node (ref "M-2") (pin "7") (pinfunction "7_7") (pintype "passive"))
      (node (ref "M-2") (pin "8") (pinfunction "8_8") (pintype "passive"))
      (node (ref "M-3") (pin "7") (pinfunction "7_7") (pintype "passive"))
      (node (ref "M-3") (pin "8") (pinfunction "8_8") (pintype "passive"))
      (node (ref "M-4") (pin "7") (pinfunction "7_7") (pintype "passive"))
      (node (ref "M-4") (pin "8") (pinfunction "8_8") (pintype "passive"))
      (node (ref "M-5") (pin "7") (pinfunction "7_7") (pintype "passive"))
      (node (ref "M-5") (pin "8") (pinfunction "8_8") (pintype "passive"))
      (node (ref "M-6") (pin "7") (pinfunction "7_7") (pintype "passive"))
      (node (ref "M-6") (pin "8") (pinfunction "8_8") (pintype "passive"))
      (node (ref "M-7") (pin "7") (pinfunction "7_7") (pintype "passive"))
      (node (ref "M-7") (pin "8") (pinfunction "8_8") (pintype "passive"))
      (node (ref "U$1") (pin "P$1") (pinfunction "P$1_P$1") (pintype "bidirectional"))
    )
    (net (code "73") (name "unconnected-(ARDUINO_DUE1-5V-Pad5V0_1)") (class "Default")
      (node (ref "ARDUINO_DUE1") (pin "5V0_1") (pinfunction "5V_5V0_1") (pintype "bidirectional"))
    )
    (net (code "74") (name "unconnected-(ARDUINO_DUE1-5V-Pad5V0_2)") (class "Default")
      (node (ref "ARDUINO_DUE1") (pin "5V0_2") (pinfunction "5V_5V0_2") (pintype "bidirectional"))
    )
    (net (code "75") (name "unconnected-(ARDUINO_DUE1-AN0-PadA0)") (class "Default")
      (node (ref "ARDUINO_DUE1") (pin "A0") (pinfunction "AN0_A0") (pintype "bidirectional"))
    )
    (net (code "76") (name "unconnected-(ARDUINO_DUE1-AN1-PadA1)") (class "Default")
      (node (ref "ARDUINO_DUE1") (pin "A1") (pinfunction "AN1_A1") (pintype "bidirectional"))
    )
    (net (code "77") (name "unconnected-(ARDUINO_DUE1-AN2-PadA2)") (class "Default")
      (node (ref "ARDUINO_DUE1") (pin "A2") (pinfunction "AN2_A2") (pintype "bidirectional"))
    )
    (net (code "78") (name "unconnected-(ARDUINO_DUE1-AN3-PadA3)") (class "Default")
      (node (ref "ARDUINO_DUE1") (pin "A3") (pinfunction "AN3_A3") (pintype "bidirectional"))
    )
    (net (code "79") (name "unconnected-(ARDUINO_DUE1-AN4-PadA4)") (class "Default")
      (node (ref "ARDUINO_DUE1") (pin "A4") (pinfunction "AN4_A4") (pintype "bidirectional"))
    )
    (net (code "80") (name "unconnected-(ARDUINO_DUE1-AN5-PadA5)") (class "Default")
      (node (ref "ARDUINO_DUE1") (pin "A5") (pinfunction "AN5_A5") (pintype "bidirectional"))
    )
    (net (code "81") (name "unconnected-(ARDUINO_DUE1-AN6-PadA6)") (class "Default")
      (node (ref "ARDUINO_DUE1") (pin "A6") (pinfunction "AN6_A6") (pintype "bidirectional"))
    )
    (net (code "82") (name "unconnected-(ARDUINO_DUE1-AN7-PadA7)") (class "Default")
      (node (ref "ARDUINO_DUE1") (pin "A7") (pinfunction "AN7_A7") (pintype "bidirectional"))
    )
    (net (code "83") (name "unconnected-(ARDUINO_DUE1-AN8-PadA8)") (class "Default")
      (node (ref "ARDUINO_DUE1") (pin "A8") (pinfunction "AN8_A8") (pintype "bidirectional"))
    )
    (net (code "84") (name "unconnected-(ARDUINO_DUE1-AN9-PadA9)") (class "Default")
      (node (ref "ARDUINO_DUE1") (pin "A9") (pinfunction "AN9_A9") (pintype "bidirectional"))
    )
    (net (code "85") (name "unconnected-(ARDUINO_DUE1-AN10-PadA10)") (class "Default")
      (node (ref "ARDUINO_DUE1") (pin "A10") (pinfunction "AN10_A10") (pintype "bidirectional"))
    )
    (net (code "86") (name "unconnected-(ARDUINO_DUE1-AN11-PadA11)") (class "Default")
      (node (ref "ARDUINO_DUE1") (pin "A11") (pinfunction "AN11_A11") (pintype "bidirectional"))
    )
    (net (code "87") (name "unconnected-(ARDUINO_DUE1-GND-PadGND_1)") (class "Default")
      (node (ref "ARDUINO_DUE1") (pin "GND_1") (pinfunction "GND_GND_1") (pintype "bidirectional"))
    )
    (net (code "88") (name "unconnected-(ARDUINO_DUE1-GND-PadGND_2)") (class "Default")
      (node (ref "ARDUINO_DUE1") (pin "GND_2") (pinfunction "GND_GND_2") (pintype "bidirectional"))
    )
    (net (code "89") (name "unconnected-(ARDUINO_DUE1-GND-PadGND_3)") (class "Default")
      (node (ref "ARDUINO_DUE1") (pin "GND_3") (pinfunction "GND_GND_3") (pintype "bidirectional"))
    )
    (net (code "90") (name "unconnected-(ARDUINO_DUE1-GND-PadGND_4)") (class "Default")
      (node (ref "ARDUINO_DUE1") (pin "GND_4") (pinfunction "GND_GND_4") (pintype "bidirectional"))
    )
    (net (code "91") (name "unconnected-(ARDUINO_DUE1-NC-PadNC_2)") (class "Default")
      (node (ref "ARDUINO_DUE1") (pin "NC_2") (pinfunction "NC_NC_2") (pintype "no_connect"))
    )
    (net (code "92") (name "unconnected-(ARDUINO_DUE1-Pad36)") (class "Default")
      (node (ref "ARDUINO_DUE1") (pin "36") (pinfunction "36_36") (pintype "bidirectional"))
    )
    (net (code "93") (name "unconnected-(ARDUINO_DUE1-Pad37)") (class "Default")
      (node (ref "ARDUINO_DUE1") (pin "37") (pinfunction "37_37") (pintype "bidirectional"))
    )
    (net (code "94") (name "unconnected-(ARDUINO_DUE1-Pad38)") (class "Default")
      (node (ref "ARDUINO_DUE1") (pin "38") (pinfunction "38_38") (pintype "bidirectional"))
    )
    (net (code "95") (name "unconnected-(ARDUINO_DUE1-Pad39)") (class "Default")
      (node (ref "ARDUINO_DUE1") (pin "39") (pinfunction "39_39") (pintype "bidirectional"))
    )
    (net (code "96") (name "unconnected-(ARDUINO_DUE1-Pad40)") (class "Default")
      (node (ref "ARDUINO_DUE1") (pin "40") (pinfunction "40_40") (pintype "bidirectional"))
    )
    (net (code "97") (name "unconnected-(ARDUINO_DUE1-Pad41)") (class "Default")
      (node (ref "ARDUINO_DUE1") (pin "41") (pinfunction "41_41") (pintype "bidirectional"))
    )
    (net (code "98") (name "unconnected-(ARDUINO_DUE1-Pad42)") (class "Default")
      (node (ref "ARDUINO_DUE1") (pin "42") (pinfunction "42_42") (pintype "bidirectional"))
    )
    (net (code "99") (name "unconnected-(ARDUINO_DUE1-Pad43)") (class "Default")
      (node (ref "ARDUINO_DUE1") (pin "43") (pinfunction "43_43") (pintype "bidirectional"))
    )
    (net (code "100") (name "unconnected-(ARDUINO_DUE1-Pad44)") (class "Default")
      (node (ref "ARDUINO_DUE1") (pin "44") (pinfunction "44_44") (pintype "bidirectional"))
    )
    (net (code "101") (name "unconnected-(ARDUINO_DUE1-Pad45)") (class "Default")
      (node (ref "ARDUINO_DUE1") (pin "45") (pinfunction "45_45") (pintype "bidirectional"))
    )
    (net (code "102") (name "unconnected-(ARDUINO_DUE1-Pad46)") (class "Default")
      (node (ref "ARDUINO_DUE1") (pin "46") (pinfunction "46_46") (pintype "bidirectional"))
    )
    (net (code "103") (name "unconnected-(ARDUINO_DUE1-Pad47)") (class "Default")
      (node (ref "ARDUINO_DUE1") (pin "47") (pinfunction "47_47") (pintype "bidirectional"))
    )
    (net (code "104") (name "unconnected-(ARDUINO_DUE1-Pad48)") (class "Default")
      (node (ref "ARDUINO_DUE1") (pin "48") (pinfunction "48_48") (pintype "bidirectional"))
    )
    (net (code "105") (name "unconnected-(ARDUINO_DUE1-Pad49)") (class "Default")
      (node (ref "ARDUINO_DUE1") (pin "49") (pinfunction "49_49") (pintype "bidirectional"))
    )
    (net (code "106") (name "unconnected-(ARDUINO_DUE1-Pad50)") (class "Default")
      (node (ref "ARDUINO_DUE1") (pin "50") (pinfunction "50_50") (pintype "bidirectional"))
    )
    (net (code "107") (name "unconnected-(ARDUINO_DUE1-Pad51)") (class "Default")
      (node (ref "ARDUINO_DUE1") (pin "51") (pinfunction "51_51") (pintype "bidirectional"))
    )
    (net (code "108") (name "unconnected-(ARDUINO_DUE1-Pad52)") (class "Default")
      (node (ref "ARDUINO_DUE1") (pin "52") (pinfunction "52_52") (pintype "bidirectional"))
    )
    (net (code "109") (name "unconnected-(ARDUINO_DUE1-Pad53)") (class "Default")
      (node (ref "ARDUINO_DUE1") (pin "53") (pinfunction "53_53") (pintype "bidirectional"))
    )
    (net (code "110") (name "unconnected-(ARDUINO_DUE1-PadAREF)") (class "Default")
      (node (ref "ARDUINO_DUE1") (pin "AREF") (pinfunction "AREF_AREF") (pintype "bidirectional"))
    )
    (net (code "111") (name "unconnected-(ARDUINO_DUE1-PadCANRX)") (class "Default")
      (node (ref "ARDUINO_DUE1") (pin "CANRX") (pinfunction "CANRX_CANRX") (pintype "bidirectional"))
    )
    (net (code "112") (name "unconnected-(ARDUINO_DUE1-PadCANTX)") (class "Default")
      (node (ref "ARDUINO_DUE1") (pin "CANTX") (pinfunction "CANTX_CANTX") (pintype "bidirectional"))
    )
    (net (code "113") (name "unconnected-(ARDUINO_DUE1-PadDAC0)") (class "Default")
      (node (ref "ARDUINO_DUE1") (pin "DAC0") (pinfunction "DAC0_DAC0") (pintype "bidirectional"))
    )
    (net (code "114") (name "unconnected-(ARDUINO_DUE1-PadDAC1)") (class "Default")
      (node (ref "ARDUINO_DUE1") (pin "DAC1") (pinfunction "DAC1_DAC1") (pintype "bidirectional"))
    )
    (net (code "115") (name "unconnected-(ARDUINO_DUE1-PadIOREF)") (class "Default")
      (node (ref "ARDUINO_DUE1") (pin "IOREF") (pinfunction "IOREF_IOREF") (pintype "bidirectional"))
    )
    (net (code "116") (name "unconnected-(ARDUINO_DUE1-PadRESET)") (class "Default")
      (node (ref "ARDUINO_DUE1") (pin "RESET") (pinfunction "RESET_RESET") (pintype "bidirectional"))
    )
    (net (code "117") (name "unconnected-(ARDUINO_DUE1-PadSCL1)") (class "Default")
      (node (ref "ARDUINO_DUE1") (pin "SCL1") (pinfunction "SCL1_SCL1") (pintype "bidirectional"))
    )
    (net (code "118") (name "unconnected-(ARDUINO_DUE1-PadSDA1)") (class "Default")
      (node (ref "ARDUINO_DUE1") (pin "SDA1") (pinfunction "SDA1_SDA1") (pintype "bidirectional"))
    )
    (net (code "119") (name "unconnected-(ARDUINO_DUE1-RX1_19-Pad19)") (class "Default")
      (node (ref "ARDUINO_DUE1") (pin "19") (pinfunction "RX1_19_19") (pintype "bidirectional"))
    )
    (net (code "120") (name "unconnected-(ARDUINO_DUE1-RX2_17-Pad17)") (class "Default")
      (node (ref "ARDUINO_DUE1") (pin "17") (pinfunction "RX2_17_17") (pintype "bidirectional"))
    )
    (net (code "121") (name "unconnected-(ARDUINO_DUE1-TX1_18-Pad18)") (class "Default")
      (node (ref "ARDUINO_DUE1") (pin "18") (pinfunction "TX1_18_18") (pintype "bidirectional"))
    )
    (net (code "122") (name "unconnected-(ARDUINO_DUE1-TX2_16-Pad16)") (class "Default")
      (node (ref "ARDUINO_DUE1") (pin "16") (pinfunction "TX2_16_16") (pintype "bidirectional"))
    )
    (net (code "123") (name "unconnected-(MD_OUT_1-Pad5)") (class "Default")
      (node (ref "MD_OUT_1") (pin "5") (pinfunction "5_5") (pintype "passive"))
    )
    (net (code "124") (name "unconnected-(MD_OUT_1-Pad6)") (class "Default")
      (node (ref "MD_OUT_1") (pin "6") (pinfunction "6_6") (pintype "passive"))
    )
    (net (code "125") (name "unconnected-(MD_OUT_1-Pad7)") (class "Default")
      (node (ref "MD_OUT_1") (pin "7") (pinfunction "7_7") (pintype "passive"))
    )
    (net (code "126") (name "unconnected-(MD_OUT_1-Pad8)") (class "Default")
      (node (ref "MD_OUT_1") (pin "8") (pinfunction "8_8") (pintype "passive"))
    )
    (net (code "127") (name "unconnected-(MD_OUT_2-Pad5)") (class "Default")
      (node (ref "MD_OUT_2") (pin "5") (pinfunction "5_5") (pintype "passive"))
    )
    (net (code "128") (name "unconnected-(MD_OUT_2-Pad6)") (class "Default")
      (node (ref "MD_OUT_2") (pin "6") (pinfunction "6_6") (pintype "passive"))
    )
    (net (code "129") (name "unconnected-(MD_OUT_2-Pad7)") (class "Default")
      (node (ref "MD_OUT_2") (pin "7") (pinfunction "7_7") (pintype "passive"))
    )
    (net (code "130") (name "unconnected-(MD_OUT_2-Pad8)") (class "Default")
      (node (ref "MD_OUT_2") (pin "8") (pinfunction "8_8") (pintype "passive"))
    )
    (net (code "131") (name "unconnected-(MD_OUT_3-Pad5)") (class "Default")
      (node (ref "MD_OUT_3") (pin "5") (pinfunction "5_5") (pintype "passive"))
    )
    (net (code "132") (name "unconnected-(MD_OUT_3-Pad6)") (class "Default")
      (node (ref "MD_OUT_3") (pin "6") (pinfunction "6_6") (pintype "passive"))
    )
    (net (code "133") (name "unconnected-(MD_OUT_3-Pad7)") (class "Default")
      (node (ref "MD_OUT_3") (pin "7") (pinfunction "7_7") (pintype "passive"))
    )
    (net (code "134") (name "unconnected-(MD_OUT_3-Pad8)") (class "Default")
      (node (ref "MD_OUT_3") (pin "8") (pinfunction "8_8") (pintype "passive"))
    )
    (net (code "135") (name "unconnected-(MD_OUT_4-Pad5)") (class "Default")
      (node (ref "MD_OUT_4") (pin "5") (pinfunction "5_5") (pintype "passive"))
    )
    (net (code "136") (name "unconnected-(MD_OUT_4-Pad6)") (class "Default")
      (node (ref "MD_OUT_4") (pin "6") (pinfunction "6_6") (pintype "passive"))
    )
    (net (code "137") (name "unconnected-(MD_OUT_4-Pad7)") (class "Default")
      (node (ref "MD_OUT_4") (pin "7") (pinfunction "7_7") (pintype "passive"))
    )
    (net (code "138") (name "unconnected-(MD_OUT_4-Pad8)") (class "Default")
      (node (ref "MD_OUT_4") (pin "8") (pinfunction "8_8") (pintype "passive"))
    )
    (net (code "139") (name "unconnected-(MD_OUT_5-Pad5)") (class "Default")
      (node (ref "MD_OUT_5") (pin "5") (pinfunction "5_5") (pintype "passive"))
    )
    (net (code "140") (name "unconnected-(MD_OUT_5-Pad6)") (class "Default")
      (node (ref "MD_OUT_5") (pin "6") (pinfunction "6_6") (pintype "passive"))
    )
    (net (code "141") (name "unconnected-(MD_OUT_5-Pad7)") (class "Default")
      (node (ref "MD_OUT_5") (pin "7") (pinfunction "7_7") (pintype "passive"))
    )
    (net (code "142") (name "unconnected-(MD_OUT_5-Pad8)") (class "Default")
      (node (ref "MD_OUT_5") (pin "8") (pinfunction "8_8") (pintype "passive"))
    )
    (net (code "143") (name "unconnected-(MD_OUT_6-Pad5)") (class "Default")
      (node (ref "MD_OUT_6") (pin "5") (pinfunction "5_5") (pintype "passive"))
    )
    (net (code "144") (name "unconnected-(MD_OUT_6-Pad6)") (class "Default")
      (node (ref "MD_OUT_6") (pin "6") (pinfunction "6_6") (pintype "passive"))
    )
    (net (code "145") (name "unconnected-(MD_OUT_6-Pad7)") (class "Default")
      (node (ref "MD_OUT_6") (pin "7") (pinfunction "7_7") (pintype "passive"))
    )
    (net (code "146") (name "unconnected-(MD_OUT_6-Pad8)") (class "Default")
      (node (ref "MD_OUT_6") (pin "8") (pinfunction "8_8") (pintype "passive"))
    )
    (net (code "147") (name "unconnected-(MD_OUT_7-Pad5)") (class "Default")
      (node (ref "MD_OUT_7") (pin "5") (pinfunction "5_5") (pintype "passive"))
    )
    (net (code "148") (name "unconnected-(MD_OUT_7-Pad6)") (class "Default")
      (node (ref "MD_OUT_7") (pin "6") (pinfunction "6_6") (pintype "passive"))
    )
    (net (code "149") (name "unconnected-(MD_OUT_7-Pad7)") (class "Default")
      (node (ref "MD_OUT_7") (pin "7") (pinfunction "7_7") (pintype "passive"))
    )
    (net (code "150") (name "unconnected-(MD_OUT_7-Pad8)") (class "Default")
      (node (ref "MD_OUT_7") (pin "8") (pinfunction "8_8") (pintype "passive"))
    )
  )
)
